# ledupper.net
KiCad netlist of a schematic drawn in EAGLE
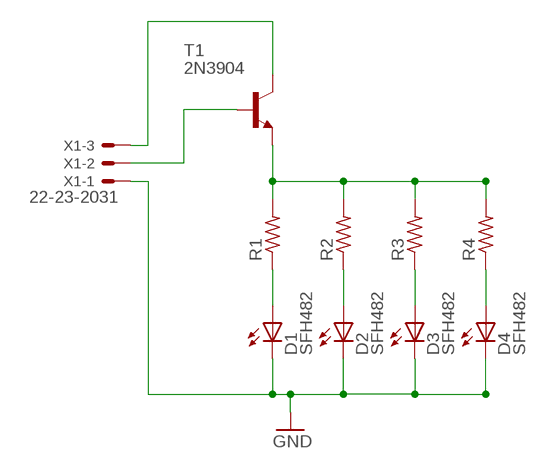
[diagram p0: schematic, sheet 1]

(export (version "E")
  (design (tool "Eeschema 10.0.6"))
  (components
    (comp (ref "D1")
      (value "SFH482")
      (footprint "eagle-import:SFH482")
      (libsource (lib "eagle-import") (part "SFH482"))
    )
    (comp (ref "D2")
      (value "SFH482")
      (footprint "eagle-import:SFH482")
      (libsource (lib "eagle-import") (part "SFH482"))
    )
    (comp (ref "D3")
      (value "SFH482")
      (footprint "eagle-import:SFH482")
      (libsource (lib "eagle-import") (part "SFH482"))
    )
    (comp (ref "D4")
      (value "SFH482")
      (footprint "eagle-import:SFH482")
      (libsource (lib "eagle-import") (part "SFH482"))
    )
    (comp (ref "R1")
      (value "R-US_0204/7")
      (footprint "eagle-import:0204_7")
      (libsource (lib "eagle-import") (part "R-US_0204/7"))
    )
    (comp (ref "R2")
      (value "R-US_0204/7")
      (footprint "eagle-import:0204_7")
      (libsource (lib "eagle-import") (part "R-US_0204/7"))
    )
    (comp (ref "R3")
      (value "R-US_0204/7")
      (footprint "eagle-import:0204_7")
      (libsource (lib "eagle-import") (part "R-US_0204/7"))
    )
    (comp (ref "R4")
      (value "R-US_0204/7")
      (footprint "eagle-import:0204_7")
      (libsource (lib "eagle-import") (part "R-US_0204/7"))
    )
    (comp (ref "T1")
      (value "2N3904")
      (footprint "eagle-import:TO92")
      (libsource (lib "eagle-import") (part "2N3904"))
    )
    (comp (ref "X1")
      (value "22-23-2031")
      (footprint "eagle-import:22-23-2031")
      (fields (field (name "MF") "MOLEX"))
      (libsource (lib "eagle-import") (part "22-23-2031"))
    )
  )
  (nets
    (net (code "1") (name "GND") (class "Default")
      (node (ref "D1") (pin "K") (pinfunction "C_K") (pintype "passive"))
      (node (ref "D2") (pin "K") (pinfunction "C_K") (pintype "passive"))
      (node (ref "D3") (pin "K") (pinfunction "C_K") (pintype "passive"))
      (node (ref "D4") (pin "K") (pinfunction "C_K") (pintype "passive"))
      (node (ref "X1") (pin "1") (pinfunction "S_1") (pintype "passive"))
    )
    (net (code "2") (name "Net-(D1-PadA)") (class "Default")
      (node (ref "D1") (pin "A") (pinfunction "A_A") (pintype "passive"))
      (node (ref "R1") (pin "1") (pinfunction "1_1") (pintype "passive"))
    )
    (net (code "3") (name "Net-(D2-PadA)") (class "Default")
      (node (ref "D2") (pin "A") (pinfunction "A_A") (pintype "passive"))
      (node (ref "R2") (pin "1") (pinfunction "1_1") (pintype "passive"))
    )
    (net (code "4") (name "Net-(D3-PadA)") (class "Default")
      (node (ref "D3") (pin "A") (pinfunction "A_A") (pintype "passive"))
      (node (ref "R3") (pin "1") (pinfunction "1_1") (pintype "passive"))
    )
    (net (code "5") (name "Net-(D4-PadA)") (class "Default")
      (node (ref "D4") (pin "A") (pinfunction "A_A") (pintype "passive"))
      (node (ref "R4") (pin "1") (pinfunction "1_1") (pintype "passive"))
    )
    (net (code "6") (name "Net-(T1-B)") (class "Default")
      (node (ref "T1") (pin "2") (pinfunction "B_2") (pintype "passive"))
      (node (ref "X1") (pin "2") (pinfunction "S_2") (pintype "passive"))
    )
    (net (code "7") (name "Net-(T1-C)") (class "Default")
      (node (ref "T1") (pin "1") (pinfunction "C_1") (pintype "passive"))
      (node (ref "X1") (pin "3") (pinfunction "S_3") (pintype "passive"))
    )
    (net (code "8") (name "Net-(T1-E)") (class "Default")
      (node (ref "R1") (pin "2") (pinfunction "2_2") (pintype "passive"))
      (node (ref "R2") (pin "2") (pinfunction "2_2") (pintype "passive"))
      (node (ref "R3") (pin "2") (pinfunction "2_2") (pintype "passive"))
      (node (ref "R4") (pin "2") (pinfunction "2_2") (pintype "passive"))
      (node (ref "T1") (pin "3") (pinfunction "E_3") (pintype "passive"))
    )
  )
)
